# main.net
KiCad netlist of a schematic drawn in EAGLE
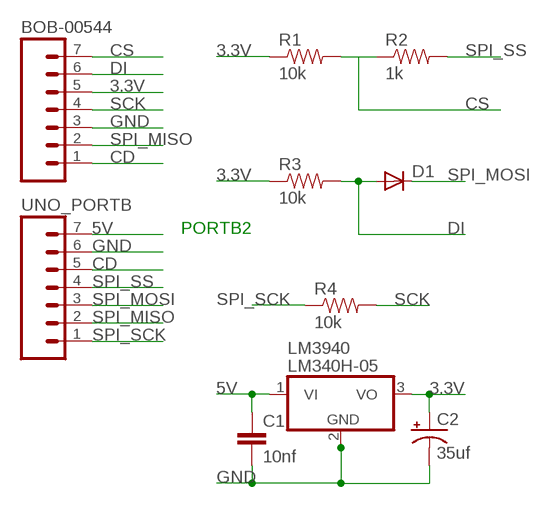
[diagram p0: schematic, sheet 1]

(export (version "E")
  (design (tool "Eeschema 10.0.6"))
  (components
    (comp (ref "BOB-00544")
      (value "M07")
      (footprint "eagle-import:1X07")
      (libsource (lib "eagle-import") (part "M07"))
    )
    (comp (ref "C1")
      (value "10nf")
      (footprint "eagle-import:CAP-PTH-SMALL")
      (libsource (lib "eagle-import") (part "CAPPTH"))
    )
    (comp (ref "C2")
      (value "35uf")
      (footprint "eagle-import:CPOL-RADIAL-100UF-25V")
      (libsource (lib "eagle-import") (part "CAP_POLPTH1"))
    )
    (comp (ref "D1")
      (value "DIODE1N4148")
      (footprint "eagle-import:DIODE-1N4148")
      (libsource (lib "eagle-import") (part "DIODE1N4148"))
    )
    (comp (ref "LM3940")
      (value "LM340H-05")
      (footprint "eagle-import:TO220H")
      (libsource (lib "eagle-import") (part "LM340?-H05"))
    )
    (comp (ref "R1")
      (value "10k")
      (footprint "eagle-import:AXIAL-0.4")
      (libsource (lib "eagle-import") (part "RESISTORPTH-1/4W"))
    )
    (comp (ref "R2")
      (value "1k")
      (footprint "eagle-import:AXIAL-0.4")
      (libsource (lib "eagle-import") (part "RESISTORPTH-1/4W"))
    )
    (comp (ref "R3")
      (value "10k")
      (footprint "eagle-import:AXIAL-0.4")
      (libsource (lib "eagle-import") (part "RESISTORPTH-1/4W"))
    )
    (comp (ref "R4")
      (value "10k")
      (footprint "eagle-import:AXIAL-0.4")
      (libsource (lib "eagle-import") (part "RESISTORPTH-1/4W"))
    )
    (comp (ref "UNO_PORTB")
      (value "M07")
      (footprint "eagle-import:1X07")
      (libsource (lib "eagle-import") (part "M07"))
    )
  )
  (nets
    (net (code "1") (name "/3.3V") (class "Default")
      (node (ref "BOB-00544") (pin "5") (pinfunction "5_5") (pintype "passive"))
      (node (ref "C2") (pin "1") (pinfunction "+_1") (pintype "passive"))
      (node (ref "LM3940") (pin "3") (pinfunction "VO_3") (pintype "passive"))
      (node (ref "R1") (pin "P$1") (pinfunction "1_P$1") (pintype "passive"))
      (node (ref "R3") (pin "P$1") (pinfunction "1_P$1") (pintype "passive"))
    )
    (net (code "2") (name "/5V") (class "Default")
      (node (ref "C1") (pin "1") (pinfunction "1_1") (pintype "passive"))
      (node (ref "LM3940") (pin "1") (pinfunction "VI_1") (pintype "input"))
      (node (ref "UNO_PORTB") (pin "7") (pinfunction "7_7") (pintype "passive"))
    )
    (net (code "3") (name "/CD") (class "Default")
      (node (ref "BOB-00544") (pin "1") (pinfunction "1_1") (pintype "passive"))
      (node (ref "UNO_PORTB") (pin "5") (pinfunction "5_5") (pintype "passive"))
    )
    (net (code "4") (name "/CS") (class "Default")
      (node (ref "BOB-00544") (pin "7") (pinfunction "7_7") (pintype "passive"))
      (node (ref "R1") (pin "P$2") (pinfunction "2_P$2") (pintype "passive"))
      (node (ref "R2") (pin "P$1") (pinfunction "1_P$1") (pintype "passive"))
    )
    (net (code "5") (name "/DI") (class "Default")
      (node (ref "BOB-00544") (pin "6") (pinfunction "6_6") (pintype "passive"))
      (node (ref "D1") (pin "A") (pinfunction "A_A") (pintype "passive"))
      (node (ref "R3") (pin "P$2") (pinfunction "2_P$2") (pintype "passive"))
    )
    (net (code "6") (name "/GND") (class "Default")
      (node (ref "BOB-00544") (pin "3") (pinfunction "3_3") (pintype "passive"))
      (node (ref "C1") (pin "2") (pinfunction "2_2") (pintype "passive"))
      (node (ref "C2") (pin "2") (pinfunction "-_2") (pintype "passive"))
      (node (ref "LM3940") (pin "2") (pinfunction "GND_2") (pintype "passive"))
      (node (ref "UNO_PORTB") (pin "6") (pinfunction "6_6") (pintype "passive"))
    )
    (net (code "7") (name "/SCK") (class "Default")
      (node (ref "BOB-00544") (pin "4") (pinfunction "4_4") (pintype "passive"))
      (node (ref "R4") (pin "P$2") (pinfunction "2_P$2") (pintype "passive"))
    )
    (net (code "8") (name "/SPI_MISO") (class "Default")
      (node (ref "BOB-00544") (pin "2") (pinfunction "2_2") (pintype "passive"))
      (node (ref "UNO_PORTB") (pin "2") (pinfunction "2_2") (pintype "passive"))
    )
    (net (code "9") (name "/SPI_MOSI") (class "Default")
      (node (ref "D1") (pin "C") (pinfunction "C_C") (pintype "passive"))
      (node (ref "UNO_PORTB") (pin "3") (pinfunction "3_3") (pintype "passive"))
    )
    (net (code "10") (name "/SPI_SCK") (class "Default")
      (node (ref "R4") (pin "P$1") (pinfunction "1_P$1") (pintype "passive"))
      (node (ref "UNO_PORTB") (pin "1") (pinfunction "1_1") (pintype "passive"))
    )
    (net (code "11") (name "/SPI_SS") (class "Default")
      (node (ref "R2") (pin "P$2") (pinfunction "2_P$2") (pintype "passive"))
      (node (ref "UNO_PORTB") (pin "4") (pinfunction "4_4") (pintype "passive"))
    )
  )
)
